# finalHDKShield.net
KiCad netlist of a schematic drawn in EAGLE
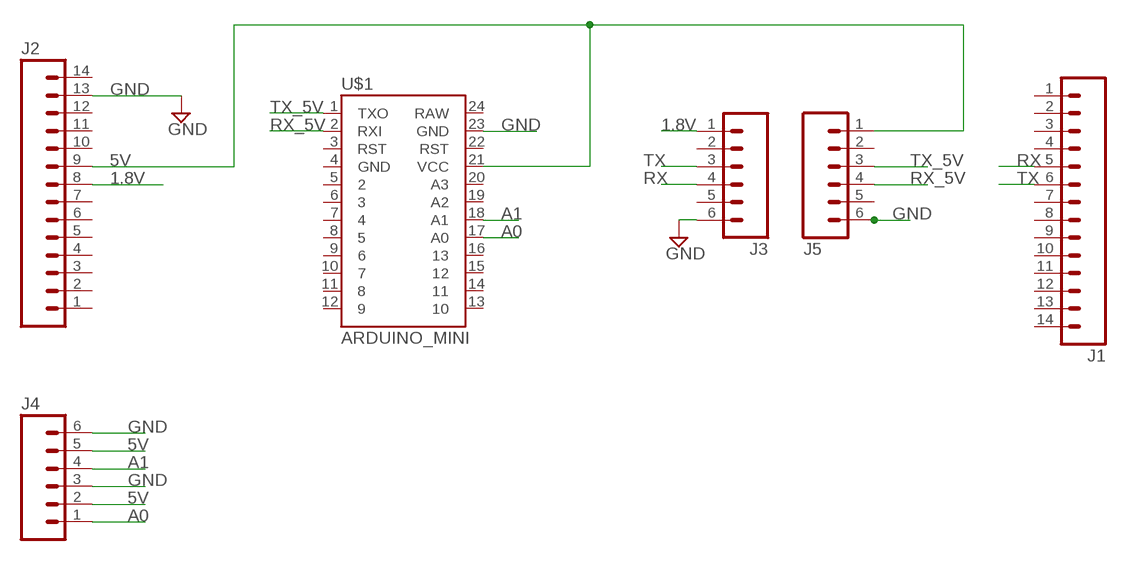
[diagram p0: schematic, sheet 1]

(export (version "E")
  (design (tool "Eeschema 10.0.6"))
  (components
    (comp (ref "J1")
      (value "M14LONGPADS")
      (footprint "eagle-import:1X14-LONGPADS")
      (libsource (lib "eagle-import") (part "M14LONGPADS"))
    )
    (comp (ref "J2")
      (value "M14LONGPADS")
      (footprint "eagle-import:1X14-LONGPADS")
      (libsource (lib "eagle-import") (part "M14LONGPADS"))
    )
    (comp (ref "J3")
      (value "M06LONGPADS")
      (footprint "eagle-import:1X06_LONGPADS")
      (libsource (lib "eagle-import") (part "M06LONGPADS"))
    )
    (comp (ref "J4")
      (value "M06LONGPADS")
      (footprint "eagle-import:1X06_LONGPADS")
      (libsource (lib "eagle-import") (part "M06LONGPADS"))
    )
    (comp (ref "J5")
      (value "M06LONGPADS")
      (footprint "eagle-import:1X06_LONGPADS")
      (libsource (lib "eagle-import") (part "M06LONGPADS"))
    )
    (comp (ref "U$1")
      (value "ARDUINO_MINI")
      (footprint "eagle-import:ARDUINO_MINI")
      (libsource (lib "eagle-import") (part "ARDUINO_MINI"))
    )
  )
  (nets
    (net (code "1") (name "/1.8V") (class "Default")
      (node (ref "J2") (pin "8") (pinfunction "8_8") (pintype "passive"))
      (node (ref "J3") (pin "1") (pinfunction "1_1") (pintype "passive"))
    )
    (net (code "2") (name "/5V") (class "Default")
      (node (ref "J2") (pin "9") (pinfunction "9_9") (pintype "passive"))
      (node (ref "J4") (pin "2") (pinfunction "2_2") (pintype "passive"))
      (node (ref "J4") (pin "5") (pinfunction "5_5") (pintype "passive"))
      (node (ref "J5") (pin "1") (pinfunction "1_1") (pintype "passive"))
      (node (ref "U$1") (pin "21") (pinfunction "VCC_21") (pintype "bidirectional"))
    )
    (net (code "3") (name "/A0") (class "Default")
      (node (ref "J4") (pin "1") (pinfunction "1_1") (pintype "passive"))
      (node (ref "U$1") (pin "17") (pinfunction "A0_17") (pintype "bidirectional"))
    )
    (net (code "4") (name "/A1") (class "Default")
      (node (ref "J4") (pin "4") (pinfunction "4_4") (pintype "passive"))
      (node (ref "U$1") (pin "18") (pinfunction "A1_18") (pintype "bidirectional"))
    )
    (net (code "5") (name "/RX") (class "Default")
      (node (ref "J1") (pin "5") (pinfunction "5_5") (pintype "passive"))
      (node (ref "J3") (pin "4") (pinfunction "4_4") (pintype "passive"))
    )
    (net (code "6") (name "/RX_5V") (class "Default")
      (node (ref "J5") (pin "4") (pinfunction "4_4") (pintype "passive"))
      (node (ref "U$1") (pin "2") (pinfunction "RXI_2") (pintype "bidirectional"))
    )
    (net (code "7") (name "/TX") (class "Default")
      (node (ref "J1") (pin "6") (pinfunction "6_6") (pintype "passive"))
      (node (ref "J3") (pin "3") (pinfunction "3_3") (pintype "passive"))
    )
    (net (code "8") (name "/TX_5V") (class "Default")
      (node (ref "J5") (pin "3") (pinfunction "3_3") (pintype "passive"))
      (node (ref "U$1") (pin "1") (pinfunction "TXO_1") (pintype "bidirectional"))
    )
    (net (code "9") (name "GND") (class "Default")
      (node (ref "J2") (pin "13") (pinfunction "13_13") (pintype "passive"))
      (node (ref "J3") (pin "6") (pinfunction "6_6") (pintype "passive"))
      (node (ref "J4") (pin "3") (pinfunction "3_3") (pintype "passive"))
      (node (ref "J4") (pin "6") (pinfunction "6_6") (pintype "passive"))
      (node (ref "J5") (pin "6") (pinfunction "6_6") (pintype "passive"))
      (node (ref "U$1") (pin "23") (pinfunction "GND_23") (pintype "bidirectional"))
    )
    (net (code "10") (name "unconnected-(J1-Pad1)") (class "Default")
      (node (ref "J1") (pin "1") (pinfunction "1_1") (pintype "passive"))
    )
    (net (code "11") (name "unconnected-(J1-Pad2)") (class "Default")
      (node (ref "J1") (pin "2") (pinfunction "2_2") (pintype "passive"))
    )
    (net (code "12") (name "unconnected-(J1-Pad3)") (class "Default")
      (node (ref "J1") (pin "3") (pinfunction "3_3") (pintype "passive"))
    )
    (net (code "13") (name "unconnected-(J1-Pad4)") (class "Default")
      (node (ref "J1") (pin "4") (pinfunction "4_4") (pintype "passive"))
    )
    (net (code "14") (name "unconnected-(J1-Pad7)") (class "Default")
      (node (ref "J1") (pin "7") (pinfunction "7_7") (pintype "passive"))
    )
    (net (code "15") (name "unconnected-(J1-Pad8)") (class "Default")
      (node (ref "J1") (pin "8") (pinfunction "8_8") (pintype "passive"))
    )
    (net (code "16") (name "unconnected-(J1-Pad9)") (class "Default")
      (node (ref "J1") (pin "9") (pinfunction "9_9") (pintype "passive"))
    )
    (net (code "17") (name "unconnected-(J1-Pad10)") (class "Default")
      (node (ref "J1") (pin "10") (pinfunction "10_10") (pintype "passive"))
    )
    (net (code "18") (name "unconnected-(J1-Pad11)") (class "Default")
      (node (ref "J1") (pin "11") (pinfunction "11_11") (pintype "passive"))
    )
    (net (code "19") (name "unconnected-(J1-Pad12)") (class "Default")
      (node (ref "J1") (pin "12") (pinfunction "12_12") (pintype "passive"))
    )
    (net (code "20") (name "unconnected-(J1-Pad13)") (class "Default")
      (node (ref "J1") (pin "13") (pinfunction "13_13") (pintype "passive"))
    )
    (net (code "21") (name "unconnected-(J1-Pad14)") (class "Default")
      (node (ref "J1") (pin "14") (pinfunction "14_14") (pintype "passive"))
    )
    (net (code "22") (name "unconnected-(J2-Pad1)") (class "Default")
      (node (ref "J2") (pin "1") (pinfunction "1_1") (pintype "passive"))
    )
    (net (code "23") (name "unconnected-(J2-Pad2)") (class "Default")
      (node (ref "J2") (pin "2") (pinfunction "2_2") (pintype "passive"))
    )
    (net (code "24") (name "unconnected-(J2-Pad3)") (class "Default")
      (node (ref "J2") (pin "3") (pinfunction "3_3") (pintype "passive"))
    )
    (net (code "25") (name "unconnected-(J2-Pad4)") (class "Default")
      (node (ref "J2") (pin "4") (pinfunction "4_4") (pintype "passive"))
    )
    (net (code "26") (name "unconnected-(J2-Pad5)") (class "Default")
      (node (ref "J2") (pin "5") (pinfunction "5_5") (pintype "passive"))
    )
    (net (code "27") (name "unconnected-(J2-Pad6)") (class "Default")
      (node (ref "J2") (pin "6") (pinfunction "6_6") (pintype "passive"))
    )
    (net (code "28") (name "unconnected-(J2-Pad7)") (class "Default")
      (node (ref "J2") (pin "7") (pinfunction "7_7") (pintype "passive"))
    )
    (net (code "29") (name "unconnected-(J2-Pad10)") (class "Default")
      (node (ref "J2") (pin "10") (pinfunction "10_10") (pintype "passive"))
    )
    (net (code "30") (name "unconnected-(J2-Pad11)") (class "Default")
      (node (ref "J2") (pin "11") (pinfunction "11_11") (pintype "passive"))
    )
    (net (code "31") (name "unconnected-(J2-Pad12)") (class "Default")
      (node (ref "J2") (pin "12") (pinfunction "12_12") (pintype "passive"))
    )
    (net (code "32") (name "unconnected-(J2-Pad14)") (class "Default")
      (node (ref "J2") (pin "14") (pinfunction "14_14") (pintype "passive"))
    )
    (net (code "33") (name "unconnected-(J3-Pad2)") (class "Default")
      (node (ref "J3") (pin "2") (pinfunction "2_2") (pintype "passive"))
    )
    (net (code "34") (name "unconnected-(J3-Pad5)") (class "Default")
      (node (ref "J3") (pin "5") (pinfunction "5_5") (pintype "passive"))
    )
    (net (code "35") (name "unconnected-(J5-Pad2)") (class "Default")
      (node (ref "J5") (pin "2") (pinfunction "2_2") (pintype "passive"))
    )
    (net (code "36") (name "unconnected-(J5-Pad5)") (class "Default")
      (node (ref "J5") (pin "5") (pinfunction "5_5") (pintype "passive"))
    )
    (net (code "37") (name "unconnected-(U$1-2-Pad5)") (class "Default")
      (node (ref "U$1") (pin "5") (pinfunction "2_5") (pintype "bidirectional"))
    )
    (net (code "38") (name "unconnected-(U$1-3-Pad6)") (class "Default")
      (node (ref "U$1") (pin "6") (pinfunction "3_6") (pintype "bidirectional"))
    )
    (net (code "39") (name "unconnected-(U$1-4-Pad7)") (class "Default")
      (node (ref "U$1") (pin "7") (pinfunction "4_7") (pintype "bidirectional"))
    )
    (net (code "40") (name "unconnected-(U$1-5-Pad8)") (class "Default")
      (node (ref "U$1") (pin "8") (pinfunction "5_8") (pintype "bidirectional"))
    )
    (net (code "41") (name "unconnected-(U$1-6-Pad9)") (class "Default")
      (node (ref "U$1") (pin "9") (pinfunction "6_9") (pintype "bidirectional"))
    )
    (net (code "42") (name "unconnected-(U$1-7-Pad10)") (class "Default")
      (node (ref "U$1") (pin "10") (pinfunction "7_10") (pintype "bidirectional"))
    )
    (net (code "43") (name "unconnected-(U$1-8-Pad11)") (class "Default")
      (node (ref "U$1") (pin "11") (pinfunction "8_11") (pintype "bidirectional"))
    )
    (net (code "44") (name "unconnected-(U$1-9-Pad12)") (class "Default")
      (node (ref "U$1") (pin "12") (pinfunction "9_12") (pintype "bidirectional"))
    )
    (net (code "45") (name "unconnected-(U$1-10-Pad13)") (class "Default")
      (node (ref "U$1") (pin "13") (pinfunction "10_13") (pintype "bidirectional"))
    )
    (net (code "46") (name "unconnected-(U$1-11-Pad14)") (class "Default")
      (node (ref "U$1") (pin "14") (pinfunction "11_14") (pintype "bidirectional"))
    )
    (net (code "47") (name "unconnected-(U$1-12-Pad15)") (class "Default")
      (node (ref "U$1") (pin "15") (pinfunction "12_15") (pintype "bidirectional"))
    )
    (net (code "48") (name "unconnected-(U$1-13-Pad16)") (class "Default")
      (node (ref "U$1") (pin "16") (pinfunction "13_16") (pintype "bidirectional"))
    )
    (net (code "49") (name "unconnected-(U$1-A2-Pad19)") (class "Default")
      (node (ref "U$1") (pin "19") (pinfunction "A2_19") (pintype "bidirectional"))
    )
    (net (code "50") (name "unconnected-(U$1-A3-Pad20)") (class "Default")
      (node (ref "U$1") (pin "20") (pinfunction "A3_20") (pintype "bidirectional"))
    )
    (net (code "51") (name "unconnected-(U$1-GND-Pad4)") (class "Default")
      (node (ref "U$1") (pin "4") (pinfunction "GND_4") (pintype "bidirectional"))
    )
    (net (code "52") (name "unconnected-(U$1-RAW-Pad24)") (class "Default")
      (node (ref "U$1") (pin "24") (pinfunction "RAW_24") (pintype "bidirectional"))
    )
    (net (code "53") (name "unconnected-(U$1-RST-Pad3)") (class "Default")
      (node (ref "U$1") (pin "3") (pinfunction "RST_3") (pintype "bidirectional"))
    )
    (net (code "54") (name "unconnected-(U$1-RST-Pad22)") (class "Default")
      (node (ref "U$1") (pin "22") (pinfunction "RST_22") (pintype "bidirectional"))
    )
  )
)
